# Power_Connection.net
KiCad netlist of a schematic drawn in Altium Designer
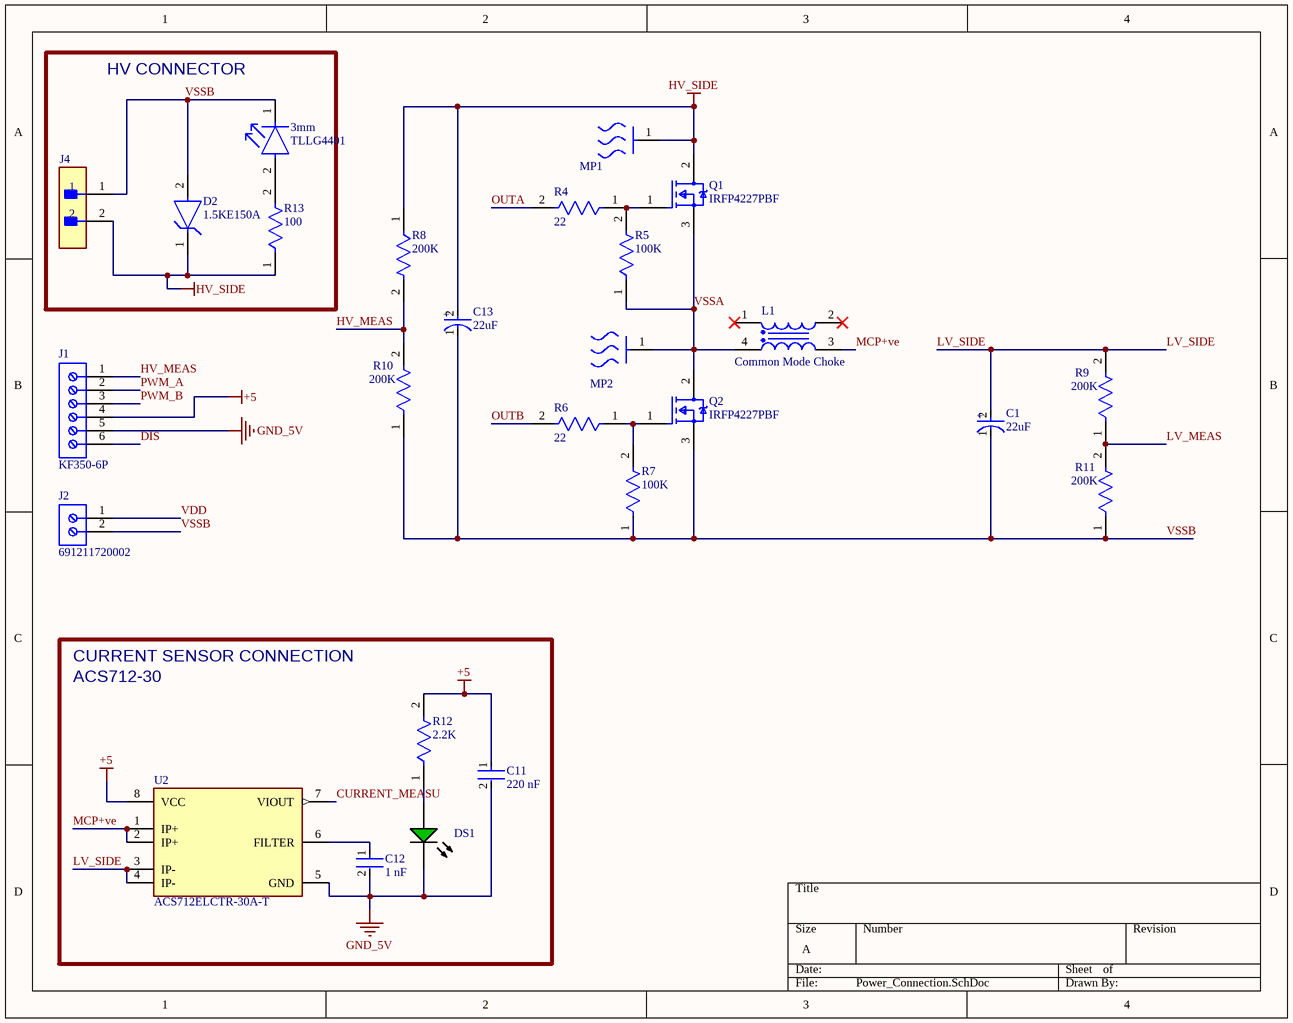
[diagram p0: Power_Connection.SchDoc]

(export (version "E")
  (design (tool "Eeschema 10.0.6"))
  (components
    (comp (ref "3mm")
      (value "TLLG4401")
      (footprint "FP-6_544-5255_01-4-MFG")
      (description "TLLG4401 LED, Green, 2mcd, 3mmDia., T-1, +/-25deg, 565nm, 7mA, 1.9V Vf, 20V Vr, 20mW, -40")
      (libsource (lib "Altium Content Vault") (part "8706943c75ba83719d021d2fdc84c58"))
    )
    (comp (ref "C1")
      (value "22uF")
      (footprint "FP-RAD-TH-D_12_5_0_5-L_20-MFG")
      (description "Aluminum Electrolytic Capacitors (Radial Lead Type) 47uF ±20% 160V")
      (fields (field (name "TOLERANCE") "20%"))
      (libsource (lib "Altium Content Vault") (part "a00bbbee19879c290e62620ae7e47b1"))
    )
    (comp (ref "C11")
      (value "220 nF")
      (footprint "FP-C0805C-DN-MFG")
      (description "CAP CER 0.22UF 50V X7R 0805")
      (fields
        (field (name "MANUFACTURER") "KEMET")
        (field (name "OCTOPART") "https://octopart.com/c0805c224k5ractu-kemet-144670")
      )
      (libsource (lib "Altium Content Vault") (part "b4654b650e69147ec39a6b967a45e02"))
    )
    (comp (ref "C12")
      (value "1 nF")
      (footprint "FP-C0805C-DN-MFG")
      (description "CAP CER 0.22UF 50V X7R 0805")
      (fields
        (field (name "MANUFACTURER") "KEMET")
        (field (name "OCTOPART") "https://octopart.com/c0805c224k5ractu-kemet-144670")
      )
      (libsource (lib "Altium Content Vault") (part "b4654b650e69147ec39a6b967a45e02"))
    )
    (comp (ref "C13")
      (value "22uF")
      (footprint "FP-RAD-TH-D_12_5_0_5-L_20-MFG")
      (description "Aluminum Electrolytic Capacitors (Radial Lead Type) 47uF ±20% 160V")
      (fields (field (name "TOLERANCE") "20%"))
      (libsource (lib "Altium Content Vault") (part "a00bbbee19879c290e62620ae7e47b1"))
    )
    (comp (ref "D2")
      (value "1.5KE150A")
      (footprint "FP-DO-201-0")
      (description "TVS DIODE 28.2V 59V DO201")
      (fields
        (field (name "MANUFACTURER") "STMicroelectronics")
        (field (name "MANUFACTURER PART NUMBER") "1.5KE33A")
      )
      (libsource (lib "Altium Content Vault") (part "7ddec9f632b8482e96f7745d0fbdf39"))
    )
    (comp (ref "DS1")
      (value "HSMG-C170")
      (footprint "AVAG-HSMX-C170_V")
      (description "Chip LED, Green, 2.2 V, -40 to 85 degC, 2-Pin SMD, Pb-Free, Tape and Reel")
      (fields (field (name "MANUFACTURER") "Avago"))
      (libsource (lib "Altium Content Vault") (part "LED_GREEN_A1K2-2"))
    )
    (comp (ref "J1")
      (value "KF350-6P")
      (footprint "PCBComponent_1")
      (libsource (lib "KF350-6P") (part "KF350-6P"))
    )
    (comp (ref "J2")
      (value "691211720002")
      (footprint "691211720002")
      (fields (field (name "VOLTAGE") "300V"))
      (libsource (lib "Altium Content Vault") (part "TBL - 1R - 02P - Screw"))
    )
    (comp (ref "J4")
      (value "B2B-XH-A(LF)(SN)")
      (footprint "FP-B2B-XH-A_LF_SN-MFG")
      (description "CONN HEADER VERT 2POS 2.5MM")
      (libsource (lib "Altium Content Vault") (part "3bc925449376181038e59eaffc5286c"))
    )
    (comp (ref "L1")
      (value "Common Mode Choke")
      (footprint "PCBComponent_1")
      (libsource (lib "R6123-X425_Choke") (part "T60405-R6123-X425"))
    )
    (comp (ref "MP1")
      (value "532702B02500G")
      (footprint "FP-532702B02500G-MFG")
      (description "HEATSINK TO-220 SOLDERPIN 50.8MM")
      (libsource (lib "Altium Content Vault") (part "6fd90e5663f104e721b9735044eea0f"))
    )
    (comp (ref "MP2")
      (value "532702B02500G")
      (footprint "FP-532702B02500G-MFG")
      (description "HEATSINK TO-220 SOLDERPIN 50.8MM")
      (libsource (lib "Altium Content Vault") (part "6fd90e5663f104e721b9735044eea0f"))
    )
    (comp (ref "Q1")
      (value "IRFP4227PBF")
      (footprint "FP-PG-TO247-3-MFG")
      (description "MOSFET N-CH 200V 65A TO247AC")
      (libsource (lib "Altium Content Vault") (part "8b62d417cbef8344eebe0bde0c45977"))
    )
    (comp (ref "Q2")
      (value "IRFP4227PBF")
      (footprint "FP-PG-TO247-3-MFG")
      (description "MOSFET N-CH 200V 65A TO247AC")
      (libsource (lib "Altium Content Vault") (part "8b62d417cbef8344eebe0bde0c45977"))
    )
    (comp (ref "R4")
      (value "22")
      (footprint "FP-VR37-MFG")
      (description "RES 1.2M OHM 5% 1/2W AXIAL")
      (fields (field (name "TOLERANCE") "5%"))
      (libsource (lib "Altium Content Vault") (part "1029c3af85768c4190bb7ad29bc67b5"))
    )
    (comp (ref "R5")
      (value "100K")
      (footprint "FP-RC0805-0_6-IPC_C")
      (description "RES 100K OHM 1% 1/8W 0805")
      (fields (field (name "TOLERANCE") "1%"))
      (libsource (lib "Altium Content Vault") (part "1029c3af85768c4190bb7ad29bc67b5"))
    )
    (comp (ref "R6")
      (value "22")
      (footprint "FP-VR37-MFG")
      (description "RES 1.2M OHM 5% 1/2W AXIAL")
      (fields (field (name "TOLERANCE") "5%"))
      (libsource (lib "Altium Content Vault") (part "1029c3af85768c4190bb7ad29bc67b5"))
    )
    (comp (ref "R7")
      (value "100K")
      (footprint "FP-RC0805-0_6-IPC_C")
      (description "RES 100K OHM 1% 1/8W 0805")
      (fields (field (name "TOLERANCE") "1%"))
      (libsource (lib "Altium Content Vault") (part "1029c3af85768c4190bb7ad29bc67b5"))
    )
    (comp (ref "R8")
      (value "200K")
      (footprint "FP-CF18-MFG")
      (description "RES 10K OHM 1/8W 5% CF AXIAL")
      (fields
        (field (name "MANUFACTURER PART NUMBER") "CF18JT10K0")
        (field (name "MANUFACTURER") "Stackpole Electronics")
      )
      (libsource (lib "Altium Content Vault") (part "1029c3af85768c4190bb7ad29bc67b5"))
    )
    (comp (ref "R9")
      (value "200K")
      (footprint "FP-CF18-MFG")
      (description "RES 10K OHM 1/8W 5% CF AXIAL")
      (fields
        (field (name "MANUFACTURER PART NUMBER") "CF18JT10K0")
        (field (name "MANUFACTURER") "Stackpole Electronics")
      )
      (libsource (lib "Altium Content Vault") (part "1029c3af85768c4190bb7ad29bc67b5"))
    )
    (comp (ref "R10")
      (value "200K")
      (footprint "FP-CF18-MFG")
      (description "RES 10K OHM 1/8W 5% CF AXIAL")
      (fields
        (field (name "MANUFACTURER PART NUMBER") "CF18JT10K0")
        (field (name "MANUFACTURER") "Stackpole Electronics")
      )
      (libsource (lib "Altium Content Vault") (part "1029c3af85768c4190bb7ad29bc67b5"))
    )
    (comp (ref "R11")
      (value "200K")
      (footprint "FP-CF18-MFG")
      (description "RES 10K OHM 1/8W 5% CF AXIAL")
      (fields
        (field (name "MANUFACTURER PART NUMBER") "CF18JT10K0")
        (field (name "MANUFACTURER") "Stackpole Electronics")
      )
      (libsource (lib "Altium Content Vault") (part "1029c3af85768c4190bb7ad29bc67b5"))
    )
    (comp (ref "R12")
      (value "2.2K")
      (footprint "FP-RC0805-0_6-IPC_C")
      (description "RES 100K OHM 1% 1/8W 0805")
      (fields (field (name "TOLERANCE") "1%"))
      (libsource (lib "Altium Content Vault") (part "1029c3af85768c4190bb7ad29bc67b5"))
    )
    (comp (ref "R13")
      (value "100")
      (footprint "FP-RC0805-0_6-IPC_C")
      (description "RES 100K OHM 1% 1/8W 0805")
      (fields (field (name "TOLERANCE") "1%"))
      (libsource (lib "Altium Content Vault") (part "1029c3af85768c4190bb7ad29bc67b5"))
    )
    (comp (ref "U2")
      (value "ACS712ELCTR-30A-T")
      (footprint "FP-LC-8-IPC_C")
      (description "SENSOR CURRENT HALL 30A AC/DC")
      (libsource (lib "Altium Content Vault") (part "a0faa98973ef06dd62ff869f1199b2d"))
    )
  )
  (nets
    (net (code "1") (name "+5") (class "Default")
      (node (ref "C11") (pin "1") (pinfunction "1_1") (pintype "passive"))
      (node (ref "J1") (pin "4") (pinfunction "4_4") (pintype "passive"))
      (node (ref "R12") (pin "2") (pinfunction "2_2") (pintype "passive"))
      (node (ref "U2") (pin "8") (pinfunction "VCC_8") (pintype "power_in"))
    )
    (net (code "2") (name "/CURRENT_MEASU") (class "Default")
      (node (ref "U2") (pin "7") (pinfunction "VIOUT_7") (pintype "output"))
    )
    (net (code "3") (name "/DIS") (class "Default")
      (node (ref "J1") (pin "6") (pinfunction "6_6") (pintype "passive"))
    )
    (net (code "4") (name "/HV_MEAS") (class "Default")
      (node (ref "J1") (pin "1") (pinfunction "1_1") (pintype "passive"))
      (node (ref "R10") (pin "2") (pinfunction "2_2") (pintype "passive"))
      (node (ref "R8") (pin "2") (pinfunction "2_2") (pintype "passive"))
    )
    (net (code "5") (name "/LV_MEAS") (class "Default")
      (node (ref "R11") (pin "2") (pinfunction "2_2") (pintype "passive"))
      (node (ref "R9") (pin "1") (pinfunction "1_1") (pintype "passive"))
    )
    (net (code "6") (name "/LV_SIDE") (class "Default")
      (node (ref "C1") (pin "2") (pinfunction "A_2") (pintype "passive"))
      (node (ref "R9") (pin "2") (pinfunction "2_2") (pintype "passive"))
      (node (ref "U2") (pin "3") (pinfunction "IP-_3") (pintype "passive"))
      (node (ref "U2") (pin "4") (pinfunction "IP-_4") (pintype "passive"))
    )
    (net (code "7") (name "/MCP+ve") (class "Default")
      (node (ref "L1") (pin "3") (pinfunction "3_3") (pintype "passive"))
      (node (ref "U2") (pin "1") (pinfunction "IP+_1") (pintype "passive"))
      (node (ref "U2") (pin "2") (pinfunction "IP+_2") (pintype "passive"))
    )
    (net (code "8") (name "/OUTA") (class "Default")
      (node (ref "R4") (pin "2") (pinfunction "2_2") (pintype "passive"))
    )
    (net (code "9") (name "/OUTB") (class "Default")
      (node (ref "R6") (pin "2") (pinfunction "2_2") (pintype "passive"))
    )
    (net (code "10") (name "/PWM_A") (class "Default")
      (node (ref "J1") (pin "2") (pinfunction "2_2") (pintype "passive"))
    )
    (net (code "11") (name "/PWM_B") (class "Default")
      (node (ref "J1") (pin "3") (pinfunction "3_3") (pintype "passive"))
    )
    (net (code "12") (name "/VDD") (class "Default")
      (node (ref "J2") (pin "1") (pinfunction "1_1") (pintype "passive"))
    )
    (net (code "13") (name "/VSSA") (class "Default")
      (node (ref "L1") (pin "4") (pinfunction "2_4") (pintype "passive"))
      (node (ref "MP2") (pin "1") (pinfunction "MNT_1_1") (pintype "passive"))
      (node (ref "Q1") (pin "3") (pinfunction "SOURCE_3") (pintype "passive"))
      (node (ref "Q2") (pin "2") (pinfunction "DRAIN_2") (pintype "passive"))
      (node (ref "R5") (pin "1") (pinfunction "1_1") (pintype "passive"))
    )
    (net (code "14") (name "/VSSB") (class "Default")
      (node (ref "3mm") (pin "1") (pinfunction "C_1") (pintype "passive"))
      (node (ref "C1") (pin "1") (pinfunction "C_1") (pintype "passive"))
      (node (ref "C13") (pin "1") (pinfunction "C_1") (pintype "passive"))
      (node (ref "D2") (pin "2") (pinfunction "A_2") (pintype "passive"))
      (node (ref "J2") (pin "2") (pinfunction "2_2") (pintype "passive"))
      (node (ref "J4") (pin "1") (pinfunction "1_1") (pintype "passive"))
      (node (ref "Q2") (pin "3") (pinfunction "SOURCE_3") (pintype "passive"))
      (node (ref "R10") (pin "1") (pinfunction "1_1") (pintype "passive"))
      (node (ref "R11") (pin "1") (pinfunction "1_1") (pintype "passive"))
      (node (ref "R7") (pin "1") (pinfunction "1_1") (pintype "passive"))
    )
    (net (code "15") (name "GND_5V") (class "Default")
      (node (ref "C11") (pin "2") (pinfunction "2_2") (pintype "passive"))
      (node (ref "C12") (pin "2") (pinfunction "2_2") (pintype "passive"))
      (node (ref "DS1") (pin "2") (pinfunction "K_2") (pintype "passive"))
      (node (ref "J1") (pin "5") (pinfunction "5_5") (pintype "passive"))
      (node (ref "U2") (pin "5") (pinfunction "GND_5") (pintype "power_in"))
    )
    (net (code "16") (name "HV_SIDE") (class "Default")
      (node (ref "C13") (pin "2") (pinfunction "A_2") (pintype "passive"))
      (node (ref "D2") (pin "1") (pinfunction "K_1") (pintype "passive"))
      (node (ref "J4") (pin "2") (pinfunction "2_2") (pintype "passive"))
      (node (ref "MP1") (pin "1") (pinfunction "MNT_1_1") (pintype "passive"))
      (node (ref "Q1") (pin "2") (pinfunction "DRAIN_2") (pintype "passive"))
      (node (ref "R13") (pin "1") (pinfunction "1_1") (pintype "passive"))
      (node (ref "R8") (pin "1") (pinfunction "1_1") (pintype "passive"))
    )
    (net (code "17") (name "Net-(3mm-A)") (class "Default")
      (node (ref "3mm") (pin "2") (pinfunction "A_2") (pintype "passive"))
      (node (ref "R13") (pin "2") (pinfunction "2_2") (pintype "passive"))
    )
    (net (code "18") (name "Net-(DS1-A)") (class "Default")
      (node (ref "DS1") (pin "1") (pinfunction "A_1") (pintype "passive"))
      (node (ref "R12") (pin "1") (pinfunction "1_1") (pintype "passive"))
    )
    (net (code "19") (name "Net-(Q1-GATE)") (class "Default")
      (node (ref "Q1") (pin "1") (pinfunction "GATE_1") (pintype "passive"))
      (node (ref "R4") (pin "1") (pinfunction "1_1") (pintype "passive"))
      (node (ref "R5") (pin "2") (pinfunction "2_2") (pintype "passive"))
    )
    (net (code "20") (name "Net-(Q2-GATE)") (class "Default")
      (node (ref "Q2") (pin "1") (pinfunction "GATE_1") (pintype "passive"))
      (node (ref "R6") (pin "1") (pinfunction "1_1") (pintype "passive"))
      (node (ref "R7") (pin "2") (pinfunction "2_2") (pintype "passive"))
    )
    (net (code "21") (name "Net-(U2-FILTER)") (class "Default")
      (node (ref "C12") (pin "1") (pinfunction "1_1") (pintype "passive"))
      (node (ref "U2") (pin "6") (pinfunction "FILTER_6") (pintype "passive"))
    )
    (net (code "22") (name "unconnected-(L1-4-Pad2)") (class "Default")
      (node (ref "L1") (pin "2") (pinfunction "4_2") (pintype "passive+no_connect"))
    )
    (net (code "23") (name "unconnected-(L1-Pad1)") (class "Default")
      (node (ref "L1") (pin "1") (pinfunction "1_1") (pintype "passive+no_connect"))
    )
  )
)
